# TransmitterBoard.net
KiCad netlist of a schematic drawn in Altium Designer
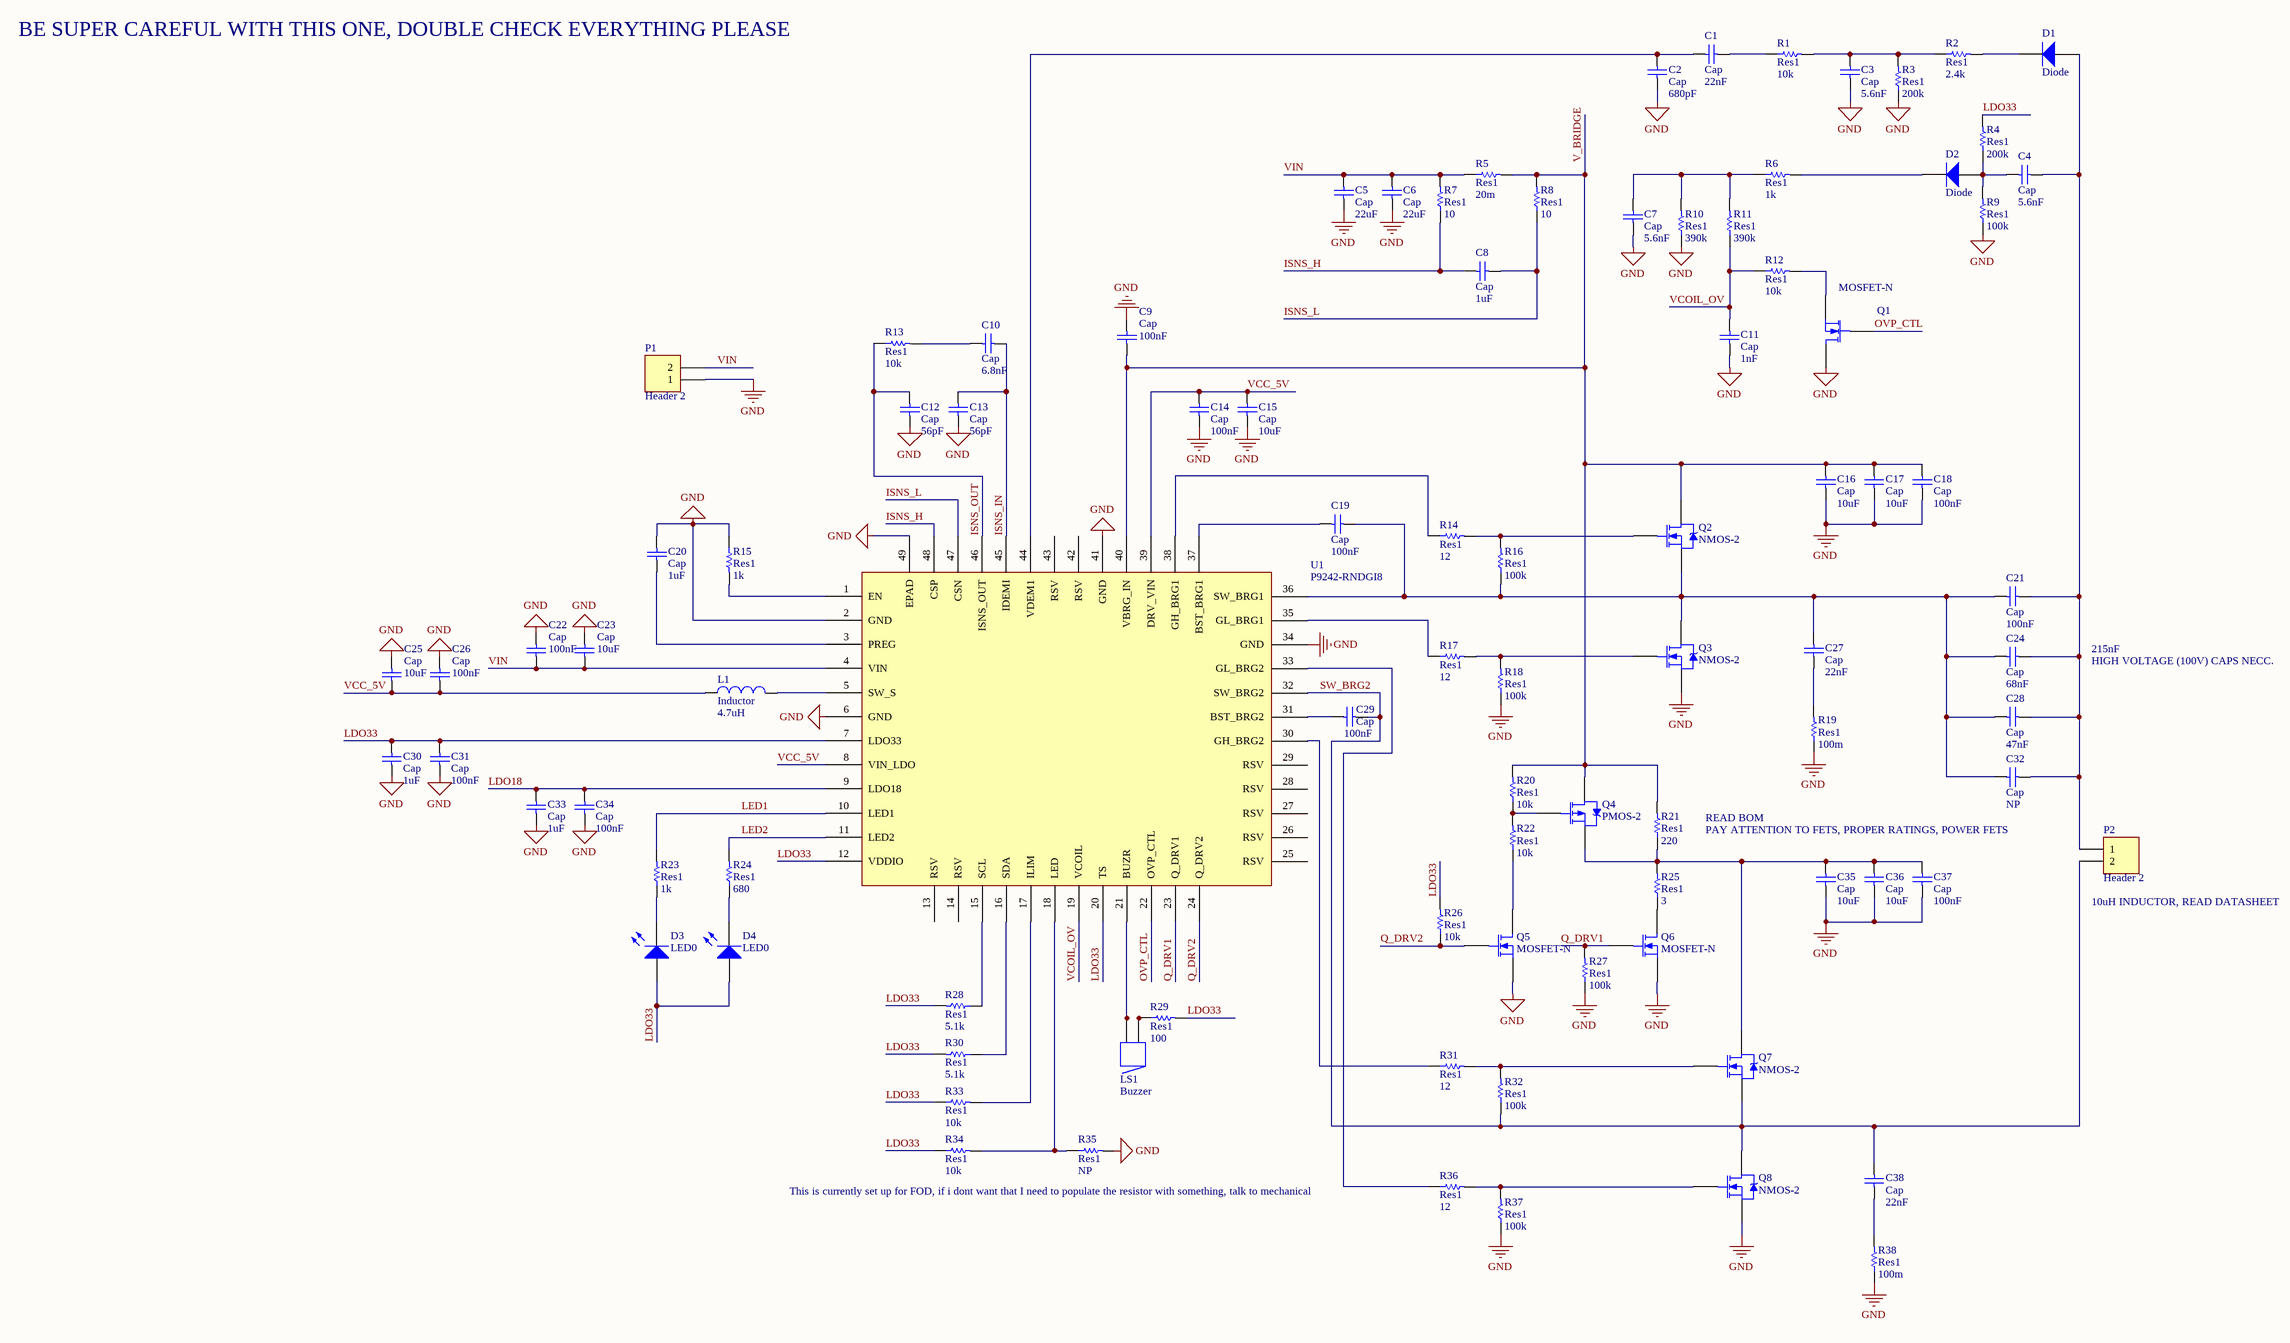
[diagram p0: TransmitterBoard.SchDoc]

(export (version "E")
  (design (tool "Eeschema 10.0.6"))
  (components
    (comp (ref "C1")
      (value "Cap")
      (footprint "1608[0603]")
      (description "Capacitor")
      (fields (field (name "ALTIUM_VALUE") "22nF") (field (name "PUBLISHER") "Altium Limited"))
      (libsource (lib "Miscellaneous Devices") (part "Cap"))
    )
    (comp (ref "C2")
      (value "Cap")
      (footprint "1608[0603]")
      (description "Capacitor")
      (fields (field (name "ALTIUM_VALUE") "680pF") (field (name "PUBLISHER") "Altium Limited"))
      (libsource (lib "Miscellaneous Devices") (part "Cap"))
    )
    (comp (ref "C3")
      (value "Cap")
      (footprint "1608[0603]")
      (description "Capacitor")
      (fields (field (name "ALTIUM_VALUE") "5.6nF") (field (name "PUBLISHER") "Altium Limited"))
      (libsource (lib "Miscellaneous Devices") (part "Cap"))
    )
    (comp (ref "C4")
      (value "Cap")
      (footprint "1608[0603]")
      (description "Capacitor")
      (fields (field (name "ALTIUM_VALUE") "5.6nF") (field (name "PUBLISHER") "Altium Limited"))
      (libsource (lib "Miscellaneous Devices") (part "Cap"))
    )
    (comp (ref "C5")
      (value "Cap")
      (footprint "C1210")
      (description "Capacitor")
      (fields (field (name "ALTIUM_VALUE") "22uF") (field (name "PUBLISHER") "Altium Limited"))
      (libsource (lib "Miscellaneous Devices") (part "Cap"))
    )
    (comp (ref "C6")
      (value "Cap")
      (footprint "C1210")
      (description "Capacitor")
      (fields (field (name "ALTIUM_VALUE") "22uF") (field (name "PUBLISHER") "Altium Limited"))
      (libsource (lib "Miscellaneous Devices") (part "Cap"))
    )
    (comp (ref "C7")
      (value "Cap")
      (footprint "1608[0603]")
      (description "Capacitor")
      (fields (field (name "ALTIUM_VALUE") "5.6nF") (field (name "PUBLISHER") "Altium Limited"))
      (libsource (lib "Miscellaneous Devices") (part "Cap"))
    )
    (comp (ref "C8")
      (value "Cap")
      (footprint "1608[0603]")
      (description "Capacitor")
      (fields (field (name "ALTIUM_VALUE") "1uF") (field (name "PUBLISHER") "Altium Limited"))
      (libsource (lib "Miscellaneous Devices") (part "Cap"))
    )
    (comp (ref "C9")
      (value "Cap")
      (footprint "1608[0603]")
      (description "Capacitor")
      (fields (field (name "ALTIUM_VALUE") "100nF") (field (name "PUBLISHER") "Altium Limited"))
      (libsource (lib "Miscellaneous Devices") (part "Cap"))
    )
    (comp (ref "C10")
      (value "Cap")
      (footprint "1608[0603]")
      (description "Capacitor")
      (fields (field (name "ALTIUM_VALUE") "6.8nF") (field (name "PUBLISHER") "Altium Limited"))
      (libsource (lib "Miscellaneous Devices") (part "Cap"))
    )
    (comp (ref "C11")
      (value "Cap")
      (footprint "1608[0603]")
      (description "Capacitor")
      (fields (field (name "ALTIUM_VALUE") "1nF") (field (name "PUBLISHER") "Altium Limited"))
      (libsource (lib "Miscellaneous Devices") (part "Cap"))
    )
    (comp (ref "C12")
      (value "Cap")
      (footprint "1608[0603]")
      (description "Capacitor")
      (fields (field (name "ALTIUM_VALUE") "56pF") (field (name "PUBLISHER") "Altium Limited"))
      (libsource (lib "Miscellaneous Devices") (part "Cap"))
    )
    (comp (ref "C13")
      (value "Cap")
      (footprint "1608[0603]")
      (description "Capacitor")
      (fields (field (name "ALTIUM_VALUE") "56pF") (field (name "PUBLISHER") "Altium Limited"))
      (libsource (lib "Miscellaneous Devices") (part "Cap"))
    )
    (comp (ref "C14")
      (value "Cap")
      (footprint "1608[0603]")
      (description "Capacitor")
      (fields (field (name "ALTIUM_VALUE") "100nF") (field (name "PUBLISHER") "Altium Limited"))
      (libsource (lib "Miscellaneous Devices") (part "Cap"))
    )
    (comp (ref "C15")
      (value "Cap")
      (footprint "6-0805_M")
      (description "Capacitor")
      (fields (field (name "ALTIUM_VALUE") "10uF") (field (name "PUBLISHER") "Altium Limited"))
      (libsource (lib "Miscellaneous Devices") (part "Cap"))
    )
    (comp (ref "C16")
      (value "Cap")
      (footprint "6-0805_M")
      (description "Capacitor")
      (fields (field (name "ALTIUM_VALUE") "10uF") (field (name "PUBLISHER") "Altium Limited"))
      (libsource (lib "Miscellaneous Devices") (part "Cap"))
    )
    (comp (ref "C17")
      (value "Cap")
      (footprint "6-0805_M")
      (description "Capacitor")
      (fields (field (name "ALTIUM_VALUE") "10uF") (field (name "PUBLISHER") "Altium Limited"))
      (libsource (lib "Miscellaneous Devices") (part "Cap"))
    )
    (comp (ref "C18")
      (value "Cap")
      (footprint "1608[0603]")
      (description "Capacitor")
      (fields (field (name "ALTIUM_VALUE") "100nF") (field (name "PUBLISHER") "Altium Limited"))
      (libsource (lib "Miscellaneous Devices") (part "Cap"))
    )
    (comp (ref "C19")
      (value "Cap")
      (footprint "1608[0603]")
      (description "Capacitor")
      (fields (field (name "ALTIUM_VALUE") "100nF") (field (name "PUBLISHER") "Altium Limited"))
      (libsource (lib "Miscellaneous Devices") (part "Cap"))
    )
    (comp (ref "C20")
      (value "Cap")
      (footprint "1608[0603]")
      (description "Capacitor")
      (fields (field (name "ALTIUM_VALUE") "1uF") (field (name "PUBLISHER") "Altium Limited"))
      (libsource (lib "Miscellaneous Devices") (part "Cap"))
    )
    (comp (ref "C21")
      (value "Cap")
      (footprint "6-0805_M")
      (description "Capacitor")
      (fields (field (name "ALTIUM_VALUE") "100nF") (field (name "PUBLISHER") "Altium Limited"))
      (libsource (lib "Miscellaneous Devices") (part "Cap"))
    )
    (comp (ref "C22")
      (value "Cap")
      (footprint "1608[0603]")
      (description "Capacitor")
      (fields (field (name "ALTIUM_VALUE") "100nF") (field (name "PUBLISHER") "Altium Limited"))
      (libsource (lib "Miscellaneous Devices") (part "Cap"))
    )
    (comp (ref "C23")
      (value "Cap")
      (footprint "6-0805_M")
      (description "Capacitor")
      (fields (field (name "ALTIUM_VALUE") "10uF") (field (name "PUBLISHER") "Altium Limited"))
      (libsource (lib "Miscellaneous Devices") (part "Cap"))
    )
    (comp (ref "C24")
      (value "Cap")
      (footprint "6-0805_M")
      (description "Capacitor")
      (fields (field (name "ALTIUM_VALUE") "68nF") (field (name "PUBLISHER") "Altium Limited"))
      (libsource (lib "Miscellaneous Devices") (part "Cap"))
    )
    (comp (ref "C25")
      (value "Cap")
      (footprint "6-0805_M")
      (description "Capacitor")
      (fields (field (name "ALTIUM_VALUE") "10uF") (field (name "PUBLISHER") "Altium Limited"))
      (libsource (lib "Miscellaneous Devices") (part "Cap"))
    )
    (comp (ref "C26")
      (value "Cap")
      (footprint "1608[0603]")
      (description "Capacitor")
      (fields (field (name "ALTIUM_VALUE") "100nF") (field (name "PUBLISHER") "Altium Limited"))
      (libsource (lib "Miscellaneous Devices") (part "Cap"))
    )
    (comp (ref "C27")
      (value "Cap")
      (footprint "1608[0603]")
      (description "Capacitor")
      (fields (field (name "ALTIUM_VALUE") "22nF") (field (name "PUBLISHER") "Altium Limited"))
      (libsource (lib "Miscellaneous Devices") (part "Cap"))
    )
    (comp (ref "C28")
      (value "Cap")
      (footprint "6-0805_M")
      (description "Capacitor")
      (fields (field (name "ALTIUM_VALUE") "47nF") (field (name "PUBLISHER") "Altium Limited"))
      (libsource (lib "Miscellaneous Devices") (part "Cap"))
    )
    (comp (ref "C29")
      (value "Cap")
      (footprint "1608[0603]")
      (description "Capacitor")
      (fields (field (name "ALTIUM_VALUE") "100nF") (field (name "PUBLISHER") "Altium Limited"))
      (libsource (lib "Miscellaneous Devices") (part "Cap"))
    )
    (comp (ref "C30")
      (value "Cap")
      (footprint "1608[0603]")
      (description "Capacitor")
      (fields (field (name "ALTIUM_VALUE") "1uF") (field (name "PUBLISHER") "Altium Limited"))
      (libsource (lib "Miscellaneous Devices") (part "Cap"))
    )
    (comp (ref "C31")
      (value "Cap")
      (footprint "1608[0603]")
      (description "Capacitor")
      (fields (field (name "ALTIUM_VALUE") "100nF") (field (name "PUBLISHER") "Altium Limited"))
      (libsource (lib "Miscellaneous Devices") (part "Cap"))
    )
    (comp (ref "C32")
      (value "Cap")
      (footprint "6-0805_M")
      (description "Capacitor")
      (fields (field (name "ALTIUM_VALUE") "NP") (field (name "PUBLISHER") "Altium Limited"))
      (libsource (lib "Miscellaneous Devices") (part "Cap"))
    )
    (comp (ref "C33")
      (value "Cap")
      (footprint "1608[0603]")
      (description "Capacitor")
      (fields (field (name "ALTIUM_VALUE") "1uF") (field (name "PUBLISHER") "Altium Limited"))
      (libsource (lib "Miscellaneous Devices") (part "Cap"))
    )
    (comp (ref "C34")
      (value "Cap")
      (footprint "1608[0603]")
      (description "Capacitor")
      (fields (field (name "ALTIUM_VALUE") "100nF") (field (name "PUBLISHER") "Altium Limited"))
      (libsource (lib "Miscellaneous Devices") (part "Cap"))
    )
    (comp (ref "C35")
      (value "Cap")
      (footprint "6-0805_M")
      (description "Capacitor")
      (fields (field (name "ALTIUM_VALUE") "10uF") (field (name "PUBLISHER") "Altium Limited"))
      (libsource (lib "Miscellaneous Devices") (part "Cap"))
    )
    (comp (ref "C36")
      (value "Cap")
      (footprint "6-0805_M")
      (description "Capacitor")
      (fields (field (name "ALTIUM_VALUE") "10uF") (field (name "PUBLISHER") "Altium Limited"))
      (libsource (lib "Miscellaneous Devices") (part "Cap"))
    )
    (comp (ref "C37")
      (value "Cap")
      (footprint "1608[0603]")
      (description "Capacitor")
      (fields (field (name "ALTIUM_VALUE") "100nF") (field (name "PUBLISHER") "Altium Limited"))
      (libsource (lib "Miscellaneous Devices") (part "Cap"))
    )
    (comp (ref "C38")
      (value "Cap")
      (footprint "1608[0603]")
      (description "Capacitor")
      (fields (field (name "ALTIUM_VALUE") "22nF") (field (name "PUBLISHER") "Altium Limited"))
      (libsource (lib "Miscellaneous Devices") (part "Cap"))
    )
    (comp (ref "D1")
      (value "Diode")
      (footprint "X3-WLB1608-2")
      (description "Default Diode")
      (fields (field (name "PUBLISHER") "Altium Limited"))
      (libsource (lib "Miscellaneous Devices") (part "Diode"))
    )
    (comp (ref "D2")
      (value "Diode")
      (footprint "X3-WLB1608-2")
      (description "Default Diode")
      (fields (field (name "PUBLISHER") "Altium Limited"))
      (libsource (lib "Miscellaneous Devices") (part "Diode"))
    )
    (comp (ref "D3")
      (value "LED0")
      (footprint "1608[0603]")
      (fields (field (name "PUBLISHER") "Altium Limited"))
      (libsource (lib "Miscellaneous Devices") (part "LED0"))
    )
    (comp (ref "D4")
      (value "LED0")
      (footprint "1608[0603]")
      (fields (field (name "PUBLISHER") "Altium Limited"))
      (libsource (lib "Miscellaneous Devices") (part "LED0"))
    )
    (comp (ref "L1")
      (value "Inductor")
      (footprint "0402-A")
      (fields (field (name "ALTIUM_VALUE") "4.7uH") (field (name "PUBLISHER") "Altium Limited"))
      (libsource (lib "Miscellaneous Devices") (part "Inductor"))
    )
    (comp (ref "LS1")
      (value "Buzzer")
      (footprint "ABSM-1574")
      (description "Magnetic Transducer Buzzer")
      (fields (field (name "PUBLISHER") "Altium Limited"))
      (libsource (lib "Miscellaneous Devices") (part "Buzzer"))
    )
    (comp (ref "P1")
      (value "Header 2")
      (footprint "2-1445096-2")
      (description "Header, 2-Pin")
      (fields (field (name "PUBLISHER") "Altium Limited"))
      (libsource (lib "Miscellaneous Connectors") (part "Header 2"))
    )
    (comp (ref "P2")
      (value "Header 2")
      (footprint "2-1445096-2")
      (description "Header, 2-Pin")
      (fields (field (name "PUBLISHER") "Altium Limited"))
      (libsource (lib "") (part "Header 2_1"))
    )
    (comp (ref "Q1")
      (value "MOSFET-N")
      (footprint "SOT23_M")
      (description "N-Channel MOSFET")
      (fields (field (name "PUBLISHER") "Altium Limited"))
      (libsource (lib "Miscellaneous Devices") (part "MOSFET-N"))
    )
    (comp (ref "Q2")
      (value "NMOS-2")
      (footprint "DMG7430LFG-7")
      (description "N-Channel Power MOSFET")
      (fields (field (name "PUBLISHER") "Altium Limited"))
      (libsource (lib "Miscellaneous Devices") (part "NMOS-2"))
    )
    (comp (ref "Q3")
      (value "NMOS-2")
      (footprint "DMG7430LFG-7")
      (description "N-Channel Power MOSFET")
      (fields (field (name "PUBLISHER") "Altium Limited"))
      (libsource (lib "Miscellaneous Devices") (part "NMOS-2"))
    )
    (comp (ref "Q4")
      (value "PMOS-2")
      (footprint "TRANS_AONR21321")
      (description "P-Channel Power MOSFET")
      (fields (field (name "PUBLISHER") "Altium Limited"))
      (libsource (lib "Miscellaneous Devices") (part "PMOS-2"))
    )
    (comp (ref "Q5")
      (value "MOSFET-N")
      (footprint "SOT23_M")
      (description "N-Channel MOSFET")
      (fields (field (name "PUBLISHER") "Altium Limited"))
      (libsource (lib "Miscellaneous Devices") (part "MOSFET-N"))
    )
    (comp (ref "Q6")
      (value "MOSFET-N")
      (footprint "SOT23_M")
      (description "N-Channel MOSFET")
      (fields (field (name "PUBLISHER") "Altium Limited"))
      (libsource (lib "Miscellaneous Devices") (part "MOSFET-N"))
    )
    (comp (ref "Q7")
      (value "NMOS-2")
      (footprint "DMG7430LFG-7")
      (description "N-Channel Power MOSFET")
      (fields (field (name "PUBLISHER") "Altium Limited"))
      (libsource (lib "Miscellaneous Devices") (part "NMOS-2"))
    )
    (comp (ref "Q8")
      (value "NMOS-2")
      (footprint "DMG7430LFG-7")
      (description "N-Channel Power MOSFET")
      (fields (field (name "PUBLISHER") "Altium Limited"))
      (libsource (lib "Miscellaneous Devices") (part "NMOS-2"))
    )
    (comp (ref "R1")
      (value "Res1")
      (footprint "1608[0603]")
      (description "Resistor")
      (fields (field (name "ALTIUM_VALUE") "10k") (field (name "PUBLISHER") "Altium Limited"))
      (libsource (lib "Miscellaneous Devices") (part "Res1"))
    )
    (comp (ref "R2")
      (value "Res1")
      (footprint "6-0805_M")
      (description "Resistor")
      (fields (field (name "ALTIUM_VALUE") "2.4k") (field (name "PUBLISHER") "Altium Limited"))
      (libsource (lib "Miscellaneous Devices") (part "Res1"))
    )
    (comp (ref "R3")
      (value "Res1")
      (footprint "6-0805_M")
      (description "Resistor")
      (fields (field (name "ALTIUM_VALUE") "200k") (field (name "PUBLISHER") "Altium Limited"))
      (libsource (lib "Miscellaneous Devices") (part "Res1"))
    )
    (comp (ref "R4")
      (value "Res1")
      (footprint "6-0805_M")
      (description "Resistor")
      (fields (field (name "ALTIUM_VALUE") "200k") (field (name "PUBLISHER") "Altium Limited"))
      (libsource (lib "Miscellaneous Devices") (part "Res1"))
    )
    (comp (ref "R5")
      (value "Res1")
      (footprint "6-0805_M")
      (description "Resistor")
      (fields (field (name "ALTIUM_VALUE") "20m") (field (name "PUBLISHER") "Altium Limited"))
      (libsource (lib "Miscellaneous Devices") (part "Res1"))
    )
    (comp (ref "R6")
      (value "Res1")
      (footprint "1608[0603]")
      (description "Resistor")
      (fields (field (name "ALTIUM_VALUE") "1k") (field (name "PUBLISHER") "Altium Limited"))
      (libsource (lib "Miscellaneous Devices") (part "Res1"))
    )
    (comp (ref "R7")
      (value "Res1")
      (footprint "6-0805_M")
      (description "Resistor")
      (fields (field (name "ALTIUM_VALUE") "10") (field (name "PUBLISHER") "Altium Limited"))
      (libsource (lib "Miscellaneous Devices") (part "Res1"))
    )
    (comp (ref "R8")
      (value "Res1")
      (footprint "6-0805_M")
      (description "Resistor")
      (fields (field (name "ALTIUM_VALUE") "10") (field (name "PUBLISHER") "Altium Limited"))
      (libsource (lib "Miscellaneous Devices") (part "Res1"))
    )
    (comp (ref "R9")
      (value "Res1")
      (footprint "1608[0603]")
      (description "Resistor")
      (fields (field (name "ALTIUM_VALUE") "100k") (field (name "PUBLISHER") "Altium Limited"))
      (libsource (lib "Miscellaneous Devices") (part "Res1"))
    )
    (comp (ref "R10")
      (value "Res1")
      (footprint "1608[0603]")
      (description "Resistor")
      (fields (field (name "ALTIUM_VALUE") "390k") (field (name "PUBLISHER") "Altium Limited"))
      (libsource (lib "Miscellaneous Devices") (part "Res1"))
    )
    (comp (ref "R11")
      (value "Res1")
      (footprint "1608[0603]")
      (description "Resistor")
      (fields (field (name "ALTIUM_VALUE") "390k") (field (name "PUBLISHER") "Altium Limited"))
      (libsource (lib "Miscellaneous Devices") (part "Res1"))
    )
    (comp (ref "R12")
      (value "Res1")
      (footprint "1608[0603]")
      (description "Resistor")
      (fields (field (name "ALTIUM_VALUE") "10k") (field (name "PUBLISHER") "Altium Limited"))
      (libsource (lib "Miscellaneous Devices") (part "Res1"))
    )
    (comp (ref "R13")
      (value "Res1")
      (footprint "1608[0603]")
      (description "Resistor")
      (fields (field (name "ALTIUM_VALUE") "10k") (field (name "PUBLISHER") "Altium Limited"))
      (libsource (lib "Miscellaneous Devices") (part "Res1"))
    )
    (comp (ref "R14")
      (value "Res1")
      (footprint "6-0805_M")
      (description "Resistor")
      (fields (field (name "ALTIUM_VALUE") "12") (field (name "PUBLISHER") "Altium Limited"))
      (libsource (lib "Miscellaneous Devices") (part "Res1"))
    )
    (comp (ref "R15")
      (value "Res1")
      (footprint "1608[0603]")
      (description "Resistor")
      (fields (field (name "ALTIUM_VALUE") "1k") (field (name "PUBLISHER") "Altium Limited"))
      (libsource (lib "Miscellaneous Devices") (part "Res1"))
    )
    (comp (ref "R16")
      (value "Res1")
      (footprint "1608[0603]")
      (description "Resistor")
      (fields (field (name "ALTIUM_VALUE") "100k") (field (name "PUBLISHER") "Altium Limited"))
      (libsource (lib "Miscellaneous Devices") (part "Res1"))
    )
    (comp (ref "R17")
      (value "Res1")
      (footprint "6-0805_M")
      (description "Resistor")
      (fields (field (name "ALTIUM_VALUE") "12") (field (name "PUBLISHER") "Altium Limited"))
      (libsource (lib "Miscellaneous Devices") (part "Res1"))
    )
    (comp (ref "R18")
      (value "Res1")
      (footprint "1608[0603]")
      (description "Resistor")
      (fields (field (name "ALTIUM_VALUE") "100k") (field (name "PUBLISHER") "Altium Limited"))
      (libsource (lib "Miscellaneous Devices") (part "Res1"))
    )
    (comp (ref "R19")
      (value "Res1")
      (footprint "6-0805_M")
      (description "Resistor")
      (fields (field (name "ALTIUM_VALUE") "100m") (field (name "PUBLISHER") "Altium Limited"))
      (libsource (lib "Miscellaneous Devices") (part "Res1"))
    )
    (comp (ref "R20")
      (value "Res1")
      (footprint "1608[0603]")
      (description "Resistor")
      (fields (field (name "ALTIUM_VALUE") "10k") (field (name "PUBLISHER") "Altium Limited"))
      (libsource (lib "Miscellaneous Devices") (part "Res1"))
    )
    (comp (ref "R21")
      (value "Res1")
      (footprint "1608[0603]")
      (description "Resistor")
      (fields (field (name "ALTIUM_VALUE") "220") (field (name "PUBLISHER") "Altium Limited"))
      (libsource (lib "Miscellaneous Devices") (part "Res1"))
    )
    (comp (ref "R22")
      (value "Res1")
      (footprint "1608[0603]")
      (description "Resistor")
      (fields (field (name "ALTIUM_VALUE") "10k") (field (name "PUBLISHER") "Altium Limited"))
      (libsource (lib "Miscellaneous Devices") (part "Res1"))
    )
    (comp (ref "R23")
      (value "Res1")
      (footprint "1608[0603]")
      (description "Resistor")
      (fields (field (name "ALTIUM_VALUE") "1k") (field (name "PUBLISHER") "Altium Limited"))
      (libsource (lib "Miscellaneous Devices") (part "Res1"))
    )
    (comp (ref "R24")
      (value "Res1")
      (footprint "6-0805_M")
      (description "Resistor")
      (fields (field (name "ALTIUM_VALUE") "680") (field (name "PUBLISHER") "Altium Limited"))
      (libsource (lib "Miscellaneous Devices") (part "Res1"))
    )
    (comp (ref "R25")
      (value "Res1")
      (footprint "6-0805_M")
      (description "Resistor")
      (fields (field (name "ALTIUM_VALUE") "3") (field (name "PUBLISHER") "Altium Limited"))
      (libsource (lib "Miscellaneous Devices") (part "Res1"))
    )
    (comp (ref "R26")
      (value "Res1")
      (footprint "1608[0603]")
      (description "Resistor")
      (fields (field (name "ALTIUM_VALUE") "10k") (field (name "PUBLISHER") "Altium Limited"))
      (libsource (lib "Miscellaneous Devices") (part "Res1"))
    )
    (comp (ref "R27")
      (value "Res1")
      (footprint "1608[0603]")
      (description "Resistor")
      (fields (field (name "ALTIUM_VALUE") "100k") (field (name "PUBLISHER") "Altium Limited"))
      (libsource (lib "Miscellaneous Devices") (part "Res1"))
    )
    (comp (ref "R28")
      (value "Res1")
      (footprint "6-0805_M")
      (description "Resistor")
      (fields (field (name "ALTIUM_VALUE") "5.1k") (field (name "PUBLISHER") "Altium Limited"))
      (libsource (lib "Miscellaneous Devices") (part "Res1"))
    )
    (comp (ref "R29")
      (value "Res1")
      (footprint "6-0805_M")
      (description "Resistor")
      (fields (field (name "ALTIUM_VALUE") "100") (field (name "PUBLISHER") "Altium Limited"))
      (libsource (lib "Miscellaneous Devices") (part "Res1"))
    )
    (comp (ref "R30")
      (value "Res1")
      (footprint "6-0805_M")
      (description "Resistor")
      (fields (field (name "ALTIUM_VALUE") "5.1k") (field (name "PUBLISHER") "Altium Limited"))
      (libsource (lib "Miscellaneous Devices") (part "Res1"))
    )
    (comp (ref "R31")
      (value "Res1")
      (footprint "6-0805_M")
      (description "Resistor")
      (fields (field (name "ALTIUM_VALUE") "12") (field (name "PUBLISHER") "Altium Limited"))
      (libsource (lib "Miscellaneous Devices") (part "Res1"))
    )
    (comp (ref "R32")
      (value "Res1")
      (footprint "1608[0603]")
      (description "Resistor")
      (fields (field (name "ALTIUM_VALUE") "100k") (field (name "PUBLISHER") "Altium Limited"))
      (libsource (lib "Miscellaneous Devices") (part "Res1"))
    )
    (comp (ref "R33")
      (value "Res1")
      (footprint "1608[0603]")
      (description "Resistor")
      (fields (field (name "ALTIUM_VALUE") "10k") (field (name "PUBLISHER") "Altium Limited"))
      (libsource (lib "Miscellaneous Devices") (part "Res1"))
    )
    (comp (ref "R34")
      (value "Res1")
      (footprint "1608[0603]")
      (description "Resistor")
      (fields (field (name "ALTIUM_VALUE") "10k") (field (name "PUBLISHER") "Altium Limited"))
      (libsource (lib "Miscellaneous Devices") (part "Res1"))
    )
    (comp (ref "R35")
      (value "Res1")
      (footprint "1608[0603]")
      (description "Resistor")
      (fields (field (name "ALTIUM_VALUE") "NP") (field (name "PUBLISHER") "Altium Limited"))
      (libsource (lib "Miscellaneous Devices") (part "Res1"))
    )
    (comp (ref "R36")
      (value "Res1")
      (footprint "6-0805_M")
      (description "Resistor")
      (fields (field (name "ALTIUM_VALUE") "12") (field (name "PUBLISHER") "Altium Limited"))
      (libsource (lib "Miscellaneous Devices") (part "Res1"))
    )
    (comp (ref "R37")
      (value "Res1")
      (footprint "1608[0603]")
      (description "Resistor")
      (fields (field (name "ALTIUM_VALUE") "100k") (field (name "PUBLISHER") "Altium Limited"))
      (libsource (lib "Miscellaneous Devices") (part "Res1"))
    )
    (comp (ref "R38")
      (value "Res1")
      (footprint "6-0805_M")
      (description "Resistor")
      (fields (field (name "ALTIUM_VALUE") "100m") (field (name "PUBLISHER") "Altium Limited"))
      (libsource (lib "Miscellaneous Devices") (part "Res1"))
    )
    (comp (ref "U1")
      (value "P9242-RNDGI8")
      (footprint "QFN40P600X600X100-49N")
      (libsource (lib "P9242") (part "Component_1"))
    )
  )
  (nets
    (net (code "2") (name "/ISNS_H") (class "Default")
      (node (ref "C8") (pin "1") (pinfunction "1_1") (pintype "passive"))
      (node (ref "R7") (pin "1") (pinfunction "1_1") (pintype "passive"))
      (node (ref "U1") (pin "48") (pinfunction "CSP_48") (pintype "passive"))
    )
    (net (code "3") (name "/ISNS_IN") (class "Default")
      (node (ref "C10") (pin "2") (pinfunction "2_2") (pintype "passive"))
      (node (ref "C13") (pin "2") (pinfunction "2_2") (pintype "passive"))
      (node (ref "U1") (pin "45") (pinfunction "IDEMI_45") (pintype "passive"))
    )
    (net (code "4") (name "/ISNS_L") (class "Default")
      (node (ref "C8") (pin "2") (pinfunction "2_2") (pintype "passive"))
      (node (ref "R8") (pin "1") (pinfunction "1_1") (pintype "passive"))
      (node (ref "U1") (pin "47") (pinfunction "CSN_47") (pintype "passive"))
    )
    (net (code "5") (name "/ISNS_OUT") (class "Default")
      (node (ref "C12") (pin "2") (pinfunction "2_2") (pintype "passive"))
      (node (ref "R13") (pin "1") (pinfunction "1_1") (pintype "passive"))
      (node (ref "U1") (pin "46") (pinfunction "ISNS_OUT_46") (pintype "passive"))
    )
    (net (code "6") (name "/LDO18") (class "Default")
      (node (ref "C33") (pin "2") (pinfunction "2_2") (pintype "passive"))
      (node (ref "C34") (pin "2") (pinfunction "2_2") (pintype "passive"))
      (node (ref "U1") (pin "9") (pinfunction "LDO18_9") (pintype "passive"))
    )
    (net (code "7") (name "/LDO33") (class "Default")
      (node (ref "C30") (pin "2") (pinfunction "2_2") (pintype "passive"))
      (node (ref "C31") (pin "2") (pinfunction "2_2") (pintype "passive"))
      (node (ref "D3") (pin "1") (pinfunction "A_1") (pintype "passive"))
      (node (ref "D4") (pin "1") (pinfunction "A_1") (pintype "passive"))
      (node (ref "R26") (pin "2") (pinfunction "2_2") (pintype "passive"))
      (node (ref "R28") (pin "2") (pinfunction "2_2") (pintype "passive"))
      (node (ref "R29") (pin "2") (pinfunction "2_2") (pintype "passive"))
      (node (ref "R30") (pin "2") (pinfunction "2_2") (pintype "passive"))
      (node (ref "R33") (pin "1") (pinfunction "1_1") (pintype "passive"))
      (node (ref "R34") (pin "1") (pinfunction "1_1") (pintype "passive"))
      (node (ref "R4") (pin "2") (pinfunction "2_2") (pintype "passive"))
      (node (ref "U1") (pin "12") (pinfunction "VDDIO_12") (pintype "passive"))
      (node (ref "U1") (pin "20") (pinfunction "TS_20") (pintype "passive"))
      (node (ref "U1") (pin "7") (pinfunction "LDO33_7") (pintype "passive"))
    )
    (net (code "8") (name "/LED1") (class "Default")
      (node (ref "R23") (pin "2") (pinfunction "2_2") (pintype "passive"))
      (node (ref "U1") (pin "10") (pinfunction "LED1_10") (pintype "passive"))
    )
    (net (code "9") (name "/LED2") (class "Default")
      (node (ref "R24") (pin "2") (pinfunction "2_2") (pintype "passive"))
      (node (ref "U1") (pin "11") (pinfunction "LED2_11") (pintype "passive"))
    )
    (net (code "10") (name "/OVP_CTL") (class "Default")
      (node (ref "Q1") (pin "2") (pinfunction "G_2") (pintype "passive"))
      (node (ref "U1") (pin "22") (pinfunction "OVP_CTL_22") (pintype "passive"))
    )
    (net (code "11") (name "/Q_DRV1") (class "Default")
      (node (ref "Q6") (pin "2") (pinfunction "G_2") (pintype "passive"))
      (node (ref "R27") (pin "2") (pinfunction "2_2") (pintype "passive"))
      (node (ref "U1") (pin "23") (pinfunction "Q_DRV1_23") (pintype "passive"))
    )
    (net (code "12") (name "/Q_DRV2") (class "Default")
      (node (ref "Q5") (pin "2") (pinfunction "G_2") (pintype "passive"))
      (node (ref "R26") (pin "1") (pinfunction "1_1") (pintype "passive"))
      (node (ref "U1") (pin "24") (pinfunction "Q_DRV2_24") (pintype "passive"))
    )
    (net (code "13") (name "/SW_BRG2") (class "Default")
      (node (ref "C29") (pin "2") (pinfunction "2_2") (pintype "passive"))
      (node (ref "C38") (pin "2") (pinfunction "2_2") (pintype "passive"))
      (node (ref "P2") (pin "2") (pinfunction "2_2") (pintype "passive"))
      (node (ref "Q7") (pin "3") (pinfunction "S_3") (pintype "passive"))
      (node (ref "Q8") (pin "2") (pinfunction "D_2") (pintype "passive"))
      (node (ref "R32") (pin "1") (pinfunction "1_1") (pintype "passive"))
      (node (ref "U1") (pin "32") (pinfunction "SW_BRG2_32") (pintype "passive"))
    )
    (net (code "14") (name "/VCC_5V") (class "Default")
      (node (ref "C14") (pin "2") (pinfunction "2_2") (pintype "passive"))
      (node (ref "C15") (pin "2") (pinfunction "2_2") (pintype "passive"))
      (node (ref "C25") (pin "2") (pinfunction "2_2") (pintype "passive"))
      (node (ref "C26") (pin "2") (pinfunction "2_2") (pintype "passive"))
      (node (ref "L1") (pin "1") (pinfunction "1_1") (pintype "passive"))
      (node (ref "U1") (pin "39") (pinfunction "DRV_VIN_39") (pintype "passive"))
      (node (ref "U1") (pin "8") (pinfunction "VIN_LDO_8") (pintype "passive"))
    )
    (net (code "15") (name "/VCOIL_OV") (class "Default")
      (node (ref "C11") (pin "2") (pinfunction "2_2") (pintype "passive"))
      (node (ref "R11") (pin "1") (pinfunction "1_1") (pintype "passive"))
      (node (ref "R12") (pin "1") (pinfunction "1_1") (pintype "passive"))
      (node (ref "U1") (pin "19") (pinfunction "VCOIL_19") (pintype "passive"))
    )
    (net (code "16") (name "/VIN") (class "Default")
      (node (ref "C22") (pin "2") (pinfunction "2_2") (pintype "passive"))
      (node (ref "C23") (pin "2") (pinfunction "2_2") (pintype "passive"))
      (node (ref "C5") (pin "2") (pinfunction "2_2") (pintype "passive"))
      (node (ref "C6") (pin "2") (pinfunction "2_2") (pintype "passive"))
      (node (ref "P1") (pin "2") (pinfunction "2_2") (pintype "passive"))
      (node (ref "R5") (pin "1") (pinfunction "1_1") (pintype "passive"))
      (node (ref "R7") (pin "2") (pinfunction "2_2") (pintype "passive"))
      (node (ref "U1") (pin "4") (pinfunction "VIN_4") (pintype "passive"))
    )
    (net (code "17") (name "/V_BRIDGE") (class "Default")
      (node (ref "C16") (pin "2") (pinfunction "2_2") (pintype "passive"))
      (node (ref "C17") (pin "2") (pinfunction "2_2") (pintype "passive"))
      (node (ref "C18") (pin "2") (pinfunction "2_2") (pintype "passive"))
      (node (ref "C9") (pin "2") (pinfunction "2_2") (pintype "passive"))
      (node (ref "Q2") (pin "2") (pinfunction "D_2") (pintype "passive"))
      (node (ref "Q4") (pin "2") (pinfunction "D_2") (pintype "passive"))
      (node (ref "R20") (pin "2") (pinfunction "2_2") (pintype "passive"))
      (node (ref "R21") (pin "2") (pinfunction "2_2") (pintype "passive"))
      (node (ref "R5") (pin "2") (pinfunction "2_2") (pintype "passive"))
      (node (ref "R8") (pin "2") (pinfunction "2_2") (pintype "passive"))
      (node (ref "U1") (pin "40") (pinfunction "VBRG_IN_40") (pintype "passive"))
    )
    (net (code "18") (name "GND") (class "Default")
      (node (ref "C11") (pin "1") (pinfunction "1_1") (pintype "passive"))
      (node (ref "C12") (pin "1") (pinfunction "1_1") (pintype "passive"))
      (node (ref "C13") (pin "1") (pinfunction "1_1") (pintype "passive"))
      (node (ref "C14") (pin "1") (pinfunction "1_1") (pintype "passive"))
      (node (ref "C15") (pin "1") (pinfunction "1_1") (pintype "passive"))
      (node (ref "C16") (pin "1") (pinfunction "1_1") (pintype "passive"))
      (node (ref "C17") (pin "1") (pinfunction "1_1") (pintype "passive"))
      (node (ref "C18") (pin "1") (pinfunction "1_1") (pintype "passive"))
      (node (ref "C2") (pin "1") (pinfunction "1_1") (pintype "passive"))
      (node (ref "C20") (pin "1") (pinfunction "1_1") (pintype "passive"))
      (node (ref "C22") (pin "1") (pinfunction "1_1") (pintype "passive"))
      (node (ref "C23") (pin "1") (pinfunction "1_1") (pintype "passive"))
      (node (ref "C25") (pin "1") (pinfunction "1_1") (pintype "passive"))
      (node (ref "C26") (pin "1") (pinfunction "1_1") (pintype "passive"))
      (node (ref "C3") (pin "1") (pinfunction "1_1") (pintype "passive"))
      (node (ref "C30") (pin "1") (pinfunction "1_1") (pintype "passive"))
      (node (ref "C31") (pin "1") (pinfunction "1_1") (pintype "passive"))
      (node (ref "C33") (pin "1") (pinfunction "1_1") (pintype "passive"))
      (node (ref "C34") (pin "1") (pinfunction "1_1") (pintype "passive"))
      (node (ref "C35") (pin "1") (pinfunction "1_1") (pintype "passive"))
      (node (ref "C36") (pin "1") (pinfunction "1_1") (pintype "passive"))
      (node (ref "C37") (pin "1") (pinfunction "1_1") (pintype "passive"))
      (node (ref "C5") (pin "1") (pinfunction "1_1") (pintype "passive"))
      (node (ref "C6") (pin "1") (pinfunction "1_1") (pintype "passive"))
      (node (ref "C7") (pin "1") (pinfunction "1_1") (pintype "passive"))
      (node (ref "C9") (pin "1") (pinfunction "1_1") (pintype "passive"))
      (node (ref "P1") (pin "1") (pinfunction "1_1") (pintype "passive"))
      (node (ref "Q1") (pin "1") (pinfunction "D_1") (pintype "passive"))
      (node (ref "Q3") (pin "3") (pinfunction "S_3") (pintype "passive"))
      (node (ref "Q5") (pin "3") (pinfunction "S_3") (pintype "passive"))
      (node (ref "Q6") (pin "3") (pinfunction "S_3") (pintype "passive"))
      (node (ref "Q8") (pin "3") (pinfunction "S_3") (pintype "passive"))
      (node (ref "R10") (pin "1") (pinfunction "1_1") (pintype "passive"))
      (node (ref "R15") (pin "1") (pinfunction "1_1") (pintype "passive"))
      (node (ref "R18") (pin "1") (pinfunction "1_1") (pintype "passive"))
      (node (ref "R19") (pin "1") (pinfunction "1_1") (pintype "passive"))
      (node (ref "R27") (pin "1") (pinfunction "1_1") (pintype "passive"))
      (node (ref "R3") (pin "1") (pinfunction "1_1") (pintype "passive"))
      (node (ref "R35") (pin "2") (pinfunction "2_2") (pintype "passive"))
      (node (ref "R37") (pin "1") (pinfunction "1_1") (pintype "passive"))
      (node (ref "R38") (pin "1") (pinfunction "1_1") (pintype "passive"))
      (node (ref "R9") (pin "1") (pinfunction "1_1") (pintype "passive"))
      (node (ref "U1") (pin "2") (pinfunction "GND_2") (pintype "passive"))
      (node (ref "U1") (pin "34") (pinfunction "GND_34") (pintype "passive"))
      (node (ref "U1") (pin "41") (pinfunction "GND_41") (pintype "passive"))
      (node (ref "U1") (pin "49") (pinfunction "EPAD_49") (pintype "passive"))
      (node (ref "U1") (pin "6") (pinfunction "GND_6") (pintype "passive"))
    )
    (net (code "19") (name "Net-(C1-Pad2)") (class "Default")
      (node (ref "C1") (pin "2") (pinfunction "2_2") (pintype "passive"))
      (node (ref "R1") (pin "1") (pinfunction "1_1") (pintype "passive"))
    )
    (net (code "20") (name "Net-(C3-Pad2)") (class "Default")
      (node (ref "C3") (pin "2") (pinfunction "2_2") (pintype "passive"))
      (node (ref "R1") (pin "2") (pinfunction "2_2") (pintype "passive"))
      (node (ref "R2") (pin "1") (pinfunction "1_1") (pintype "passive"))
      (node (ref "R3") (pin "2") (pinfunction "2_2") (pintype "passive"))
    )
    (net (code "21") (name "Net-(C7-Pad2)") (class "Default")
      (node (ref "C7") (pin "2") (pinfunction "2_2") (pintype "passive"))
      (node (ref "R10") (pin "2") (pinfunction "2_2") (pintype "passive"))
      (node (ref "R11") (pin "2") (pinfunction "2_2") (pintype "passive"))
      (node (ref "R6") (pin "1") (pinfunction "1_1") (pintype "passive"))
    )
    (net (code "22") (name "Net-(C10-Pad1)") (class "Default")
      (node (ref "C10") (pin "1") (pinfunction "1_1") (pintype "passive"))
      (node (ref "R13") (pin "2") (pinfunction "2_2") (pintype "passive"))
    )
    (net (code "23") (name "Net-(C27-Pad1)") (class "Default")
      (node (ref "C27") (pin "1") (pinfunction "1_1") (pintype "passive"))
      (node (ref "R19") (pin "2") (pinfunction "2_2") (pintype "passive"))
    )
    (net (code "24") (name "Net-(C38-Pad1)") (class "Default")
      (node (ref "C38") (pin "1") (pinfunction "1_1") (pintype "passive"))
      (node (ref "R38") (pin "2") (pinfunction "2_2") (pintype "passive"))
    )
    (net (code "25") (name "Net-(D1-A)") (class "Default")
      (node (ref "C21") (pin "2") (pinfunction "2_2") (pintype "passive"))
      (node (ref "C24") (pin "2") (pinfunction "2_2") (pintype "passive"))
      (node (ref "C28") (pin "2") (pinfunction "2_2") (pintype "passive"))
      (node (ref "C32") (pin "2") (pinfunction "2_2") (pintype "passive"))
      (node (ref "C4") (pin "2") (pinfunction "2_2") (pintype "passive"))
      (node (ref "D1") (pin "1") (pinfunction "A_1") (pintype "passive"))
      (node (ref "P2") (pin "1") (pinfunction "1_1") (pintype "passive"))
    )
    (net (code "26") (name "Net-(D1-K)") (class "Default")
      (node (ref "D1") (pin "2") (pinfunction "K_2") (pintype "passive"))
      (node (ref "R2") (pin "2") (pinfunction "2_2") (pintype "passive"))
    )
    (net (code "27") (name "Net-(D2-A)") (class "Default")
      (node (ref "C4") (pin "1") (pinfunction "1_1") (pintype "passive"))
      (node (ref "D2") (pin "1") (pinfunction "A_1") (pintype "passive"))
      (node (ref "R4") (pin "1") (pinfunction "1_1") (pintype "passive"))
      (node (ref "R9") (pin "2") (pinfunction "2_2") (pintype "passive"))
    )
    (net (code "28") (name "Net-(D2-K)") (class "Default")
      (node (ref "D2") (pin "2") (pinfunction "K_2") (pintype "passive"))
      (node (ref "R6") (pin "2") (pinfunction "2_2") (pintype "passive"))
    )
    (net (code "29") (name "Net-(D3-K)") (class "Default")
      (node (ref "D3") (pin "2") (pinfunction "K_2") (pintype "passive"))
      (node (ref "R23") (pin "1") (pinfunction "1_1") (pintype "passive"))
    )
    (net (code "30") (name "Net-(D4-K)") (class "Default")
      (node (ref "D4") (pin "2") (pinfunction "K_2") (pintype "passive"))
      (node (ref "R24") (pin "1") (pinfunction "1_1") (pintype "passive"))
    )
    (net (code "31") (name "Net-(LS1-Pad1)") (class "Default")
      (node (ref "LS1") (pin "1") (pinfunction "1_1") (pintype "passive"))
      (node (ref "LS1") (pin "1A") (pinfunction "1A_1A") (pintype "passive"))
      (node (ref "R29") (pin "1") (pinfunction "1_1") (pintype "passive"))
    )
    (net (code "32") (name "Net-(Q1-S)") (class "Default")
      (node (ref "Q1") (pin "3") (pinfunction "S_3") (pintype "passive"))
      (node (ref "R12") (pin "2") (pinfunction "2_2") (pintype "passive"))
    )
    (net (code "33") (name "Net-(Q2-G)") (class "Default")
      (node (ref "Q2") (pin "1") (pinfunction "G_1") (pintype "passive"))
      (node (ref "R14") (pin "2") (pinfunction "2_2") (pintype "passive"))
      (node (ref "R16") (pin "2") (pinfunction "2_2") (pintype "passive"))
    )
    (net (code "34") (name "Net-(Q2-S)") (class "Default")
      (node (ref "C19") (pin "2") (pinfunction "2_2") (pintype "passive"))
      (node (ref "C21") (pin "1") (pinfunction "1_1") (pintype "passive"))
      (node (ref "C24") (pin "1") (pinfunction "1_1") (pintype "passive"))
      (node (ref "C27") (pin "2") (pinfunction "2_2") (pintype "passive"))
      (node (ref "C28") (pin "1") (pinfunction "1_1") (pintype "passive"))
      (node (ref "C32") (pin "1") (pinfunction "1_1") (pintype "passive"))
      (node (ref "Q2") (pin "3") (pinfunction "S_3") (pintype "passive"))
      (node (ref "Q3") (pin "2") (pinfunction "D_2") (pintype "passive"))
      (node (ref "R16") (pin "1") (pinfunction "1_1") (pintype "passive"))
      (node (ref "U1") (pin "36") (pinfunction "SW_BRG1_36") (pintype "passive"))
    )
    (net (code "35") (name "Net-(Q3-G)") (class "Default")
      (node (ref "Q3") (pin "1") (pinfunction "G_1") (pintype "passive"))
      (node (ref "R17") (pin "2") (pinfunction "2_2") (pintype "passive"))
      (node (ref "R18") (pin "2") (pinfunction "2_2") (pintype "passive"))
    )
    (net (code "36") (name "Net-(Q4-G)") (class "Default")
      (node (ref "Q4") (pin "1") (pinfunction "G_1") (pintype "passive"))
      (node (ref "R20") (pin "1") (pinfunction "1_1") (pintype "passive"))
      (node (ref "R22") (pin "2") (pinfunction "2_2") (pintype "passive"))
    )
    (net (code "37") (name "Net-(Q4-S)") (class "Default")
      (node (ref "C35") (pin "2") (pinfunction "2_2") (pintype "passive"))
      (node (ref "C36") (pin "2") (pinfunction "2_2") (pintype "passive"))
      (node (ref "C37") (pin "2") (pinfunction "2_2") (pintype "passive"))
      (node (ref "Q4") (pin "3") (pinfunction "S_3") (pintype "passive"))
      (node (ref "Q7") (pin "2") (pinfunction "D_2") (pintype "passive"))
      (node (ref "R21") (pin "1") (pinfunction "1_1") (pintype "passive"))
      (node (ref "R25") (pin "2") (pinfunction "2_2") (pintype "passive"))
    )
    (net (code "38") (name "Net-(Q5-D)") (class "Default")
      (node (ref "Q5") (pin "1") (pinfunction "D_1") (pintype "passive"))
      (node (ref "R22") (pin "1") (pinfunction "1_1") (pintype "passive"))
    )
    (net (code "39") (name "Net-(Q6-D)") (class "Default")
      (node (ref "Q6") (pin "1") (pinfunction "D_1") (pintype "passive"))
      (node (ref "R25") (pin "1") (pinfunction "1_1") (pintype "passive"))
    )
    (net (code "40") (name "Net-(Q7-G)") (class "Default")
      (node (ref "Q7") (pin "1") (pinfunction "G_1") (pintype "passive"))
      (node (ref "R31") (pin "2") (pinfunction "2_2") (pintype "passive"))
      (node (ref "R32") (pin "2") (pinfunction "2_2") (pintype "passive"))
    )
    (net (code "41") (name "Net-(Q8-G)") (class "Default")
      (node (ref "Q8") (pin "1") (pinfunction "G_1") (pintype "passive"))
      (node (ref "R36") (pin "2") (pinfunction "2_2") (pintype "passive"))
      (node (ref "R37") (pin "2") (pinfunction "2_2") (pintype "passive"))
    )
    (net (code "42") (name "Net-(U1-BST_BRG1)") (class "Default")
      (node (ref "C19") (pin "1") (pinfunction "1_1") (pintype "passive"))
      (node (ref "U1") (pin "37") (pinfunction "BST_BRG1_37") (pintype "passive"))
    )
    (net (code "43") (name "Net-(U1-BST_BRG2)") (class "Default")
      (node (ref "C29") (pin "1") (pinfunction "1_1") (pintype "passive"))
      (node (ref "U1") (pin "31") (pinfunction "BST_BRG2_31") (pintype "passive"))
    )
    (net (code "44") (name "Net-(U1-BUZR)") (class "Default")
      (node (ref "LS1") (pin "2") (pinfunction "2_2") (pintype "passive"))
      (node (ref "LS1") (pin "2A") (pinfunction "2A_2A") (pintype "passive"))
      (node (ref "U1") (pin "21") (pinfunction "BUZR_21") (pintype "passive"))
    )
    (net (code "45") (name "Net-(U1-EN)") (class "Default")
      (node (ref "R15") (pin "2") (pinfunction "2_2") (pintype "passive"))
      (node (ref "U1") (pin "1") (pinfunction "EN_1") (pintype "passive"))
    )
    (net (code "46") (name "Net-(U1-GH_BRG1)") (class "Default")
      (node (ref "R14") (pin "1") (pinfunction "1_1") (pintype "passive"))
      (node (ref "U1") (pin "38") (pinfunction "GH_BRG1_38") (pintype "passive"))
    )
    (net (code "47") (name "Net-(U1-GH_BRG2)") (class "Default")
      (node (ref "R31") (pin "1") (pinfunction "1_1") (pintype "passive"))
      (node (ref "U1") (pin "30") (pinfunction "GH_BRG2_30") (pintype "passive"))
    )
    (net (code "48") (name "Net-(U1-GL_BRG1)") (class "Default")
      (node (ref "R17") (pin "1") (pinfunction "1_1") (pintype "passive"))
      (node (ref "U1") (pin "35") (pinfunction "GL_BRG1_35") (pintype "passive"))
    )
    (net (code "49") (name "Net-(U1-GL_BRG2)") (class "Default")
      (node (ref "R36") (pin "1") (pinfunction "1_1") (pintype "passive"))
      (node (ref "U1") (pin "33") (pinfunction "GL_BRG2_33") (pintype "passive"))
    )
    (net (code "50") (name "Net-(U1-ILIM)") (class "Default")
      (node (ref "R33") (pin "2") (pinfunction "2_2") (pintype "passive"))
      (node (ref "U1") (pin "17") (pinfunction "ILIM_17") (pintype "passive"))
    )
    (net (code "51") (name "Net-(U1-LED)") (class "Default")
      (node (ref "R34") (pin "2") (pinfunction "2_2") (pintype "passive"))
      (node (ref "R35") (pin "1") (pinfunction "1_1") (pintype "passive"))
      (node (ref "U1") (pin "18") (pinfunction "LED_18") (pintype "passive"))
    )
    (net (code "52") (name "Net-(U1-PREG)") (class "Default")
      (node (ref "C20") (pin "2") (pinfunction "2_2") (pintype "passive"))
      (node (ref "U1") (pin "3") (pinfunction "PREG_3") (pintype "passive"))
    )
    (net (code "53") (name "Net-(U1-SCL)") (class "Default")
      (node (ref "R28") (pin "1") (pinfunction "1_1") (pintype "passive"))
      (node (ref "U1") (pin "15") (pinfunction "SCL_15") (pintype "passive"))
    )
    (net (code "54") (name "Net-(U1-SDA)") (class "Default")
      (node (ref "R30") (pin "1") (pinfunction "1_1") (pintype "passive"))
      (node (ref "U1") (pin "16") (pinfunction "SDA_16") (pintype "passive"))
    )
    (net (code "55") (name "Net-(U1-SW_S)") (class "Default")
      (node (ref "L1") (pin "2") (pinfunction "2_2") (pintype "passive"))
      (node (ref "U1") (pin "5") (pinfunction "SW_S_5") (pintype "passive"))
    )
    (net (code "56") (name "Net-(U1-VDEM1)") (class "Default")
      (node (ref "C1") (pin "1") (pinfunction "1_1") (pintype "passive"))
      (node (ref "C2") (pin "2") (pinfunction "2_2") (pintype "passive"))
      (node (ref "U1") (pin "44") (pinfunction "VDEM1_44") (pintype "passive"))
    )
    (net (code "57") (name "unconnected-(U1-RSV-Pad13)") (class "Default")
      (node (ref "U1") (pin "13") (pinfunction "RSV_13") (pintype "passive"))
    )
    (net (code "58") (name "unconnected-(U1-RSV-Pad14)") (class "Default")
      (node (ref "U1") (pin "14") (pinfunction "RSV_14") (pintype "passive"))
    )
    (net (code "59") (name "unconnected-(U1-RSV-Pad25)") (class "Default")
      (node (ref "U1") (pin "25") (pinfunction "RSV_25") (pintype "passive"))
    )
    (net (code "60") (name "unconnected-(U1-RSV-Pad26)") (class "Default")
      (node (ref "U1") (pin "26") (pinfunction "RSV_26") (pintype "passive"))
    )
    (net (code "61") (name "unconnected-(U1-RSV-Pad27)") (class "Default")
      (node (ref "U1") (pin "27") (pinfunction "RSV_27") (pintype "passive"))
    )
    (net (code "62") (name "unconnected-(U1-RSV-Pad28)") (class "Default")
      (node (ref "U1") (pin "28") (pinfunction "RSV_28") (pintype "passive"))
    )
    (net (code "63") (name "unconnected-(U1-RSV-Pad29)") (class "Default")
      (node (ref "U1") (pin "29") (pinfunction "RSV_29") (pintype "passive"))
    )
    (net (code "64") (name "unconnected-(U1-RSV-Pad42)") (class "Default")
      (node (ref "U1") (pin "42") (pinfunction "RSV_42") (pintype "passive"))
    )
    (net (code "65") (name "unconnected-(U1-RSV-Pad43)") (class "Default")
      (node (ref "U1") (pin "43") (pinfunction "RSV_43") (pintype "passive"))
    )
  )
)
